# pressure_foot.net
KiCad netlist of a schematic drawn in EAGLE
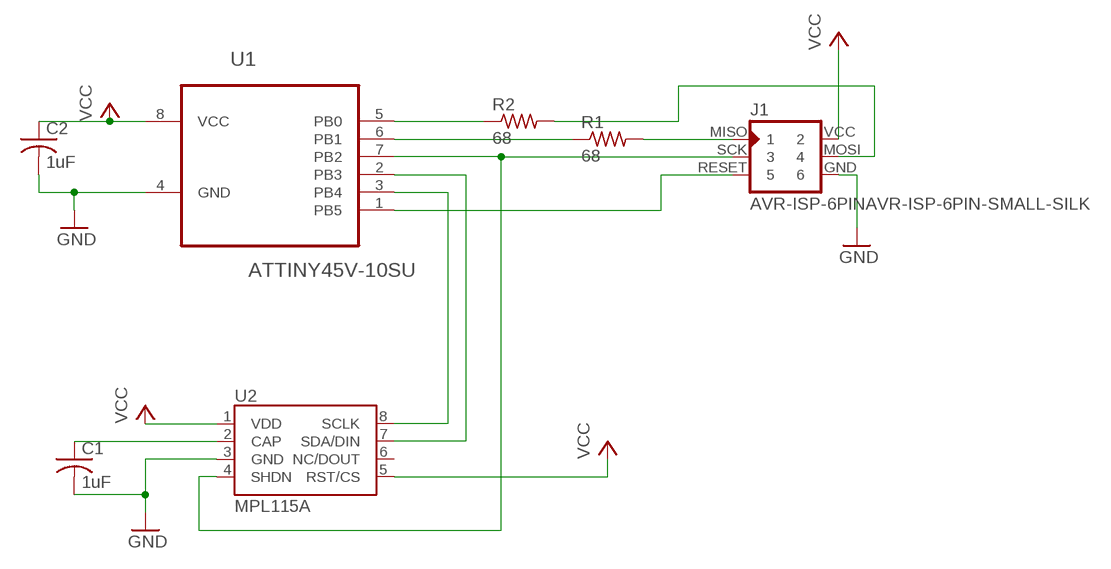
[diagram p0: schematic, sheet 1]

(export (version "E")
  (design (tool "Eeschema 10.0.6"))
  (components
    (comp (ref "C1")
      (value "1uF")
      (footprint "eagle-import:C0603")
      (libsource (lib "eagle-import") (part "C-USC0603"))
    )
    (comp (ref "C2")
      (value "1uF")
      (footprint "eagle-import:C0603")
      (libsource (lib "eagle-import") (part "C-USC0603"))
    )
    (comp (ref "J1")
      (value "AVR-ISP-6PINAVR-ISP-6PIN-SMALL-SILK")
      (footprint "eagle-import:AVR-ISP-6PIN-SMAILL-SILK")
      (libsource (lib "eagle-import") (part "AVR-ISP-6PINAVR-ISP-6PIN-SMALL-SILK"))
    )
    (comp (ref "R1")
      (value "68")
      (footprint "eagle-import:R0603")
      (libsource (lib "eagle-import") (part "R-US_R0603"))
    )
    (comp (ref "R2")
      (value "68")
      (footprint "eagle-import:R0603")
      (libsource (lib "eagle-import") (part "R-US_R0603"))
    )
    (comp (ref "U1")
      (value "ATTINY45V-10SU")
      (footprint "eagle-import:SOIC127P798X216-8N")
      (libsource (lib "eagle-import") (part "ATTINY45V-10SU"))
    )
    (comp (ref "U2")
      (value "MPL115A")
      (footprint "eagle-import:LGA8")
      (libsource (lib "eagle-import") (part "MPL115A"))
    )
  )
  (nets
    (net (code "1") (name "GND") (class "Default")
      (node (ref "C1") (pin "2") (pinfunction "2_2") (pintype "passive"))
      (node (ref "C2") (pin "2") (pinfunction "2_2") (pintype "passive"))
      (node (ref "J1") (pin "GND") (pinfunction "6_GND") (pintype "passive"))
      (node (ref "U1") (pin "4") (pinfunction "GND_4") (pintype "passive"))
      (node (ref "U2") (pin "3") (pinfunction "GND_3") (pintype "bidirectional"))
    )
    (net (code "2") (name "Net-(J1-1)") (class "Default")
      (node (ref "J1") (pin "MISO") (pinfunction "1_MISO") (pintype "passive"))
      (node (ref "R1") (pin "2") (pinfunction "2_2") (pintype "passive"))
    )
    (net (code "3") (name "Net-(J1-3)") (class "Default")
      (node (ref "J1") (pin "SCK") (pinfunction "3_SCK") (pintype "passive"))
      (node (ref "U1") (pin "7") (pinfunction "PB2_7") (pintype "bidirectional"))
      (node (ref "U2") (pin "4") (pinfunction "SHDN_4") (pintype "bidirectional"))
    )
    (net (code "4") (name "Net-(J1-4)") (class "Default")
      (node (ref "J1") (pin "MOSI") (pinfunction "4_MOSI") (pintype "passive"))
      (node (ref "R2") (pin "2") (pinfunction "2_2") (pintype "passive"))
    )
    (net (code "5") (name "Net-(J1-5)") (class "Default")
      (node (ref "J1") (pin "RESET") (pinfunction "5_RESET") (pintype "passive"))
      (node (ref "U1") (pin "1") (pinfunction "PB5_1") (pintype "bidirectional"))
    )
    (net (code "6") (name "Net-(U1-PB0)") (class "Default")
      (node (ref "R2") (pin "1") (pinfunction "1_1") (pintype "passive"))
      (node (ref "U1") (pin "5") (pinfunction "PB0_5") (pintype "bidirectional"))
    )
    (net (code "7") (name "Net-(U1-PB1)") (class "Default")
      (node (ref "R1") (pin "1") (pinfunction "1_1") (pintype "passive"))
      (node (ref "U1") (pin "6") (pinfunction "PB1_6") (pintype "bidirectional"))
    )
    (net (code "8") (name "Net-(U1-PB3)") (class "Default")
      (node (ref "U1") (pin "2") (pinfunction "PB3_2") (pintype "bidirectional"))
      (node (ref "U2") (pin "7") (pinfunction "SDA/DIN_7") (pintype "bidirectional"))
    )
    (net (code "9") (name "Net-(U1-PB4)") (class "Default")
      (node (ref "U1") (pin "3") (pinfunction "PB4_3") (pintype "bidirectional"))
      (node (ref "U2") (pin "8") (pinfunction "SCLK_8") (pintype "bidirectional"))
    )
    (net (code "10") (name "Net-(U2-CAP)") (class "Default")
      (node (ref "C1") (pin "1") (pinfunction "1_1") (pintype "passive"))
      (node (ref "U2") (pin "2") (pinfunction "CAP_2") (pintype "bidirectional"))
    )
    (net (code "11") (name "VCC") (class "Default")
      (node (ref "C2") (pin "1") (pinfunction "1_1") (pintype "passive"))
      (node (ref "J1") (pin "VCC") (pinfunction "2_VCC") (pintype "passive"))
      (node (ref "U1") (pin "8") (pinfunction "VCC_8") (pintype "power_in"))
      (node (ref "U2") (pin "1") (pinfunction "VDD_1") (pintype "bidirectional"))
      (node (ref "U2") (pin "5") (pinfunction "RST/CS_5") (pintype "bidirectional"))
    )
    (net (code "12") (name "unconnected-(U2-NC{slash}DOUT-Pad6)") (class "Default")
      (node (ref "U2") (pin "6") (pinfunction "NC/DOUT_6") (pintype "bidirectional"))
    )
  )
)
